# Sheet1.net
KiCad netlist of a schematic drawn in Altium Designer
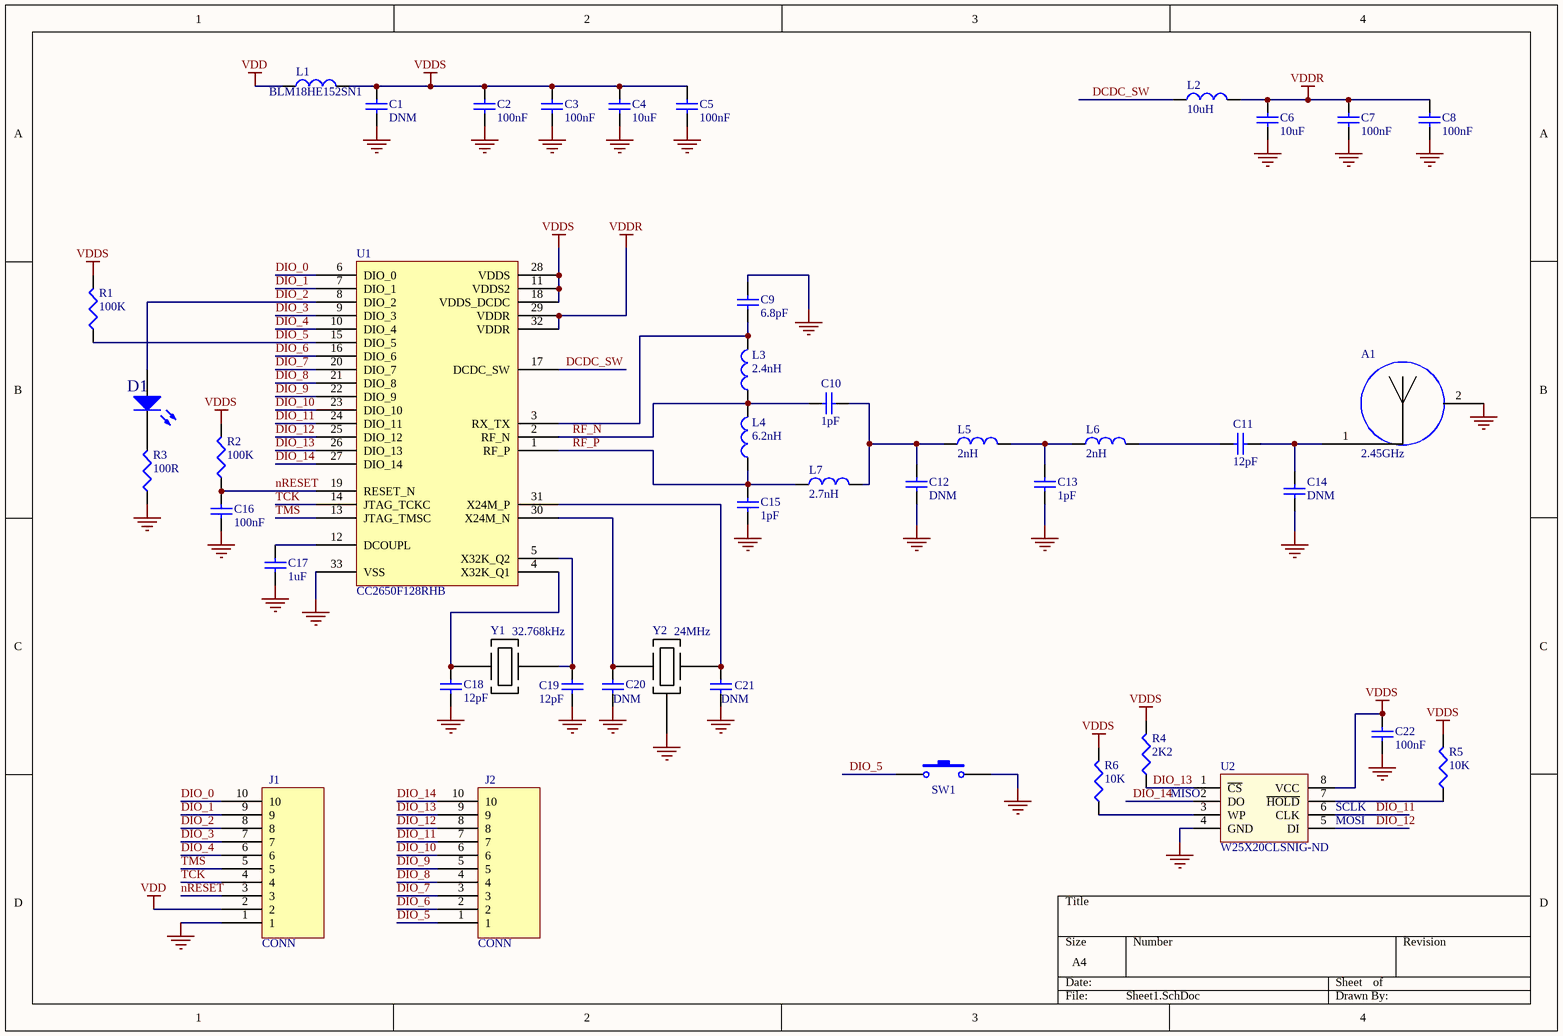
[diagram p0: Sheet1.SchDoc]

(export (version "E")
  (design (tool "Eeschema 10.0.6"))
  (components
    (comp (ref "A1")
      (value "2.45GHz")
      (footprint "ANTENNA_PCB_INATEL3")
      (description "ANTENNA 2.4GHz Freescale reference")
      (libsource (lib "Mechanical") (part "ANTENNA 2.4GHz_INATEL"))
    )
    (comp (ref "C1") (value "DNM") (footprint "0402") (libsource (lib "Schlib1") (part "CAP")))
    (comp (ref "C2")
      (value "100nF")
      (footprint "0402 - CAP")
      (description "CAP CER 0.1UF 6.3V 10% X7R 0402")
      (fields (field (name "MANUFACTURER") "Murata"))
      (libsource (lib "Schlib1") (part "CAP"))
    )
    (comp (ref "C3")
      (value "100nF")
      (footprint "0402 - CAP")
      (description "CAP CER 0.1UF 6.3V 10% X7R 0402")
      (fields (field (name "MANUFACTURER") "Murata"))
      (libsource (lib "Schlib1") (part "CAP"))
    )
    (comp (ref "C4")
      (value "10uF")
      (footprint "0603 - CAP")
      (description "CAP CER 10UF 6.3V 20% X5R 0603")
      (fields (field (name "MANUFACTURER") "Murata"))
      (libsource (lib "Schlib1") (part "CAP"))
    )
    (comp (ref "C5")
      (value "100nF")
      (footprint "0402 - CAP")
      (description "CAP CER 0.1UF 6.3V 10% X7R 0402")
      (fields (field (name "MANUFACTURER") "Murata"))
      (libsource (lib "Schlib1") (part "CAP"))
    )
    (comp (ref "C6")
      (value "10uF")
      (footprint "0603 - CAP")
      (description "CAP CER 10UF 6.3V 20% X5R 0603")
      (fields (field (name "MANUFACTURER") "Murata"))
      (libsource (lib "Schlib1") (part "CAP"))
    )
    (comp (ref "C7")
      (value "100nF")
      (footprint "0402 - CAP")
      (description "CAP CER 0.1UF 6.3V 10% X7R 0402")
      (fields (field (name "MANUFACTURER") "Murata"))
      (libsource (lib "Schlib1") (part "CAP"))
    )
    (comp (ref "C8")
      (value "100nF")
      (footprint "0402 - CAP")
      (description "CAP CER 0.1UF 6.3V 10% X7R 0402")
      (fields (field (name "MANUFACTURER") "Murata"))
      (libsource (lib "Schlib1") (part "CAP"))
    )
    (comp (ref "C9")
      (value "6.8pF")
      (footprint "0402 - CAP")
      (description "CAP CER 6.8PF 50V NP0 0402")
      (fields (field (name "MANUFACTURER") "Murata"))
      (libsource (lib "Schlib1") (part "CAP"))
    )
    (comp (ref "C10")
      (value "1pF")
      (footprint "0402 - CAP")
      (description "CAP CER 1PF 50V NP0 0402")
      (fields (field (name "MANUFACTURER") "Murata"))
      (libsource (lib "Schlib1") (part "CAP"))
    )
    (comp (ref "C11")
      (value "12pF")
      (footprint "0402 - CAP")
      (description "CAP CER 12PF 50V NP0 0402")
      (fields (field (name "MANUFACTURER") "Murata"))
      (libsource (lib "Schlib1") (part "CAP"))
    )
    (comp (ref "C12") (value "DNM") (footprint "0402") (libsource (lib "Schlib1") (part "CAP")))
    (comp (ref "C13")
      (value "1pF")
      (footprint "0402 - CAP")
      (description "CAP CER 1PF 50V NP0 0402")
      (fields (field (name "MANUFACTURER") "Murata"))
      (libsource (lib "Schlib1") (part "CAP"))
    )
    (comp (ref "C14") (value "DNM") (footprint "0402") (libsource (lib "Schlib1") (part "CAP")))
    (comp (ref "C15")
      (value "1pF")
      (footprint "0402 - CAP")
      (description "CAP CER 1PF 50V NP0 0402")
      (fields (field (name "MANUFACTURER") "Murata"))
      (libsource (lib "Schlib1") (part "CAP"))
    )
    (comp (ref "C16")
      (value "100nF")
      (footprint "0402 - CAP")
      (description "CAP CER 0.1UF 6.3V 10% X7R 0402")
      (fields (field (name "MANUFACTURER") "Murata"))
      (libsource (lib "Schlib1") (part "CAP"))
    )
    (comp (ref "C17")
      (value "1uF")
      (footprint "0402 - CAP")
      (description "CAP CER 1UF 10V 10% X5R 0402")
      (fields (field (name "MANUFACTURER") "Murata"))
      (libsource (lib "Schlib1") (part "CAP"))
    )
    (comp (ref "C18")
      (value "12pF")
      (footprint "0402 - CAP")
      (description "CAP CER 12PF 50V NP0 0402")
      (fields (field (name "MANUFACTURER") "Murata"))
      (libsource (lib "Schlib1") (part "CAP"))
    )
    (comp (ref "C19")
      (value "12pF")
      (footprint "0402 - CAP")
      (description "CAP CER 12PF 50V NP0 0402")
      (fields (field (name "MANUFACTURER") "Murata"))
      (libsource (lib "Schlib1") (part "CAP"))
    )
    (comp (ref "C20") (value "DNM") (footprint "0402") (libsource (lib "Schlib1") (part "CAP")))
    (comp (ref "C21") (value "DNM") (footprint "0402") (libsource (lib "Schlib1") (part "CAP")))
    (comp (ref "C22")
      (value "100nF")
      (footprint "0402 - CAP")
      (description "CAP CER 0.1UF 6.3V 10% X7R 0402")
      (fields (field (name "MANUFACTURER") "Murata"))
      (libsource (lib "Schlib1") (part "CAP"))
    )
    (comp (ref "D1")
      (value "Status")
      (footprint "0603 - LED")
      (description "LED SUPER RED CLR THIN 0603 SMD")
      (fields (field (name "MANUFACTURER") "Lite-On Inc"))
      (libsource (lib "Schlib1") (part "LED_R"))
    )
    (comp (ref "J1")
      (value "CONN")
      (footprint "CONN_HEADER ARDUINO SHIELD")
      (description "10POS SIL VERTICAL PIN HEADER")
      (fields (field (name "MANUFACTURER") "Harwin Inc"))
      (libsource (lib "Schlib1") (part "CONN"))
    )
    (comp (ref "J2")
      (value "CONN")
      (footprint "CONN_HEADER ARDUINO SHIELD")
      (description "10POS SIL VERTICAL PIN HEADER")
      (fields (field (name "MANUFACTURER") "Harwin Inc"))
      (libsource (lib "Schlib1") (part "CONN"))
    )
    (comp (ref "L1")
      (value "BLM18HE152SN1")
      (footprint "0603 - IND")
      (description "FERRITE CHIP 1500 OHM 500MA 0603")
      (fields (field (name "MANUFACTURER") "Murata"))
      (libsource (lib "Schlib1") (part "INDUCTOR"))
    )
    (comp (ref "L2")
      (value "10uH")
      (footprint "0805 - CAP")
      (description "FIXED IND 10UH 110MA 520 MOHM")
      (fields (field (name "MANUFACTURER") "Taiyo Yuden"))
      (libsource (lib "Schlib1") (part "INDUCTOR"))
    )
    (comp (ref "L3")
      (value "2.4nH")
      (footprint "0402 - IND")
      (description "FIXED IND 2.4NH 300MA 160 MOHM")
      (fields (field (name "MANUFACTURER") "Murata"))
      (libsource (lib "") (part "INDUCTOR_1"))
    )
    (comp (ref "L4")
      (value "6.2nH")
      (footprint "0402 - IND")
      (description "FIXED IND 6.2NH 300MA 220 MOHM")
      (fields (field (name "MANUFACTURER") "Murata"))
      (libsource (lib "Schlib1") (part "INDUCTOR"))
    )
    (comp (ref "L5")
      (value "2nH")
      (footprint "0402 - IND")
      (description "FIXED IND 2NH 300MA 100 MOHM SMD")
      (fields (field (name "MANUFACTURER") "Murata"))
      (libsource (lib "Schlib1") (part "INDUCTOR"))
    )
    (comp (ref "L6")
      (value "2nH")
      (footprint "0402 - IND")
      (description "FIXED IND 2NH 300MA 100 MOHM SMD")
      (fields (field (name "MANUFACTURER") "Murata"))
      (libsource (lib "Schlib1") (part "INDUCTOR"))
    )
    (comp (ref "L7")
      (value "2.7nH")
      (footprint "0402 - IND")
      (description "FIXED IND 2.7NH 300MA 150 MOHM")
      (fields (field (name "MANUFACTURER") "Murata"))
      (libsource (lib "Schlib1") (part "INDUCTOR"))
    )
    (comp (ref "R1")
      (value "100K")
      (footprint "0402 - RES")
      (description "RES SMD 100K OHM 5% 1/10W 0402")
      (fields (field (name "MANUFACTURER") "Panasonic"))
      (libsource (lib "Schlib1") (part "RES"))
    )
    (comp (ref "R2")
      (value "100K")
      (footprint "0402 - RES")
      (description "RES SMD 100K OHM 5% 1/10W 0402")
      (fields (field (name "MANUFACTURER") "Panasonic"))
      (libsource (lib "Schlib1") (part "RES"))
    )
    (comp (ref "R3")
      (value "100R")
      (footprint "0402 - RES")
      (description "RES SMD 100 OHM 5% 1/10W 0402")
      (fields (field (name "MANUFACTURER") "Panasonic"))
      (libsource (lib "Schlib1") (part "RES"))
    )
    (comp (ref "R4")
      (value "2K2")
      (footprint "0402 - RES")
      (description "RES SMD 2.2K OHM 5% 1/10W 0402")
      (fields (field (name "MANUFACTURER") "Panasonic"))
      (libsource (lib "Schlib1") (part "RES"))
    )
    (comp (ref "R5")
      (value "10K")
      (footprint "0402 - RES")
      (description "RES SMD 10K OHM 5% 1/10W 0402")
      (fields (field (name "MANUFACTURER") "Panasonic"))
      (libsource (lib "Schlib1") (part "RES"))
    )
    (comp (ref "R6")
      (value "10K")
      (footprint "0402 - RES")
      (description "RES SMD 10K OHM 5% 1/10W 0402")
      (fields (field (name "MANUFACTURER") "Panasonic"))
      (libsource (lib "Schlib1") (part "RES"))
    )
    (comp (ref "SW1")
      (value "~")
      (footprint "EVP-AWCA2A")
      (description "SW")
      (libsource (lib "Mechanical") (part "SW_EVPAW"))
    )
    (comp (ref "U1")
      (value "CC2650F128RHB")
      (footprint "CC2650F128RHB - cm")
      (description "IC MCU 128KB FLASH PHY 32VQFN")
      (fields (field (name "MANUFACTURER") "TI"))
      (libsource (lib "Schlib1") (part "CC2650F128RHB"))
    )
    (comp (ref "U2")
      (value "W25X20CLSNIG-ND")
      (footprint "SOIC-8")
      (description "IC FLASH 2MBIT 104MHZ 8SOIC")
      (fields (field (name "MANUFACTURER") "Winbond"))
      (libsource (lib "Schlib1") (part "SPI_FLASH_SOIC_8"))
    )
    (comp (ref "Y1")
      (value "32.768kHz")
      (footprint "FC-12M")
      (description "Crystal 32.7680kHz 20ppm 12.5pF 90 kOhm -40°C - 85°C Surface Mount 2-SMD")
      (fields (field (name "MANUFACTURER") "EPSON"))
      (libsource (lib "") (part "XTAL1_1"))
    )
    (comp (ref "Y2")
      (value "24MHz")
      (footprint "XT_DFN_LCC_32x25")
      (description "Crystal 24.0000MHz 10ppm 9pF 40 Ohm -40°C - 85°C Surface Mount 4-SMD, No Lead (DFN, LCC)")
      (fields (field (name "MANUFACTURER") "EPSON"))
      (libsource (lib "Schlib1") (part "XTAL1"))
    )
  )
  (nets
    (net (code "1") (name "/DCDC_SW") (class "Default")
      (node (ref "L2") (pin "2") (pinfunction "2_2") (pintype "passive"))
      (node (ref "U1") (pin "17") (pinfunction "DCDC_SW_17") (pintype "passive"))
    )
    (net (code "2") (name "/DIO_0") (class "Default")
      (node (ref "J2") (pin "10") (pinfunction "10_10") (pintype "passive"))
      (node (ref "U1") (pin "6") (pinfunction "DIO_0_6") (pintype "passive"))
    )
    (net (code "3") (name "/DIO_1") (class "Default")
      (node (ref "J2") (pin "9") (pinfunction "9_9") (pintype "passive"))
      (node (ref "U1") (pin "7") (pinfunction "DIO_1_7") (pintype "passive"))
    )
    (net (code "4") (name "/DIO_2") (class "Default")
      (node (ref "D1") (pin "1") (pinfunction "A_1") (pintype "passive"))
      (node (ref "J2") (pin "8") (pinfunction "8_8") (pintype "passive"))
      (node (ref "U1") (pin "8") (pinfunction "DIO_2_8") (pintype "passive"))
    )
    (net (code "5") (name "/DIO_3") (class "Default")
      (node (ref "J2") (pin "7") (pinfunction "7_7") (pintype "passive"))
      (node (ref "U1") (pin "9") (pinfunction "DIO_3_9") (pintype "passive"))
    )
    (net (code "6") (name "/DIO_4") (class "Default")
      (node (ref "J2") (pin "6") (pinfunction "6_6") (pintype "passive"))
      (node (ref "U1") (pin "10") (pinfunction "DIO_4_10") (pintype "passive"))
    )
    (net (code "7") (name "/DIO_5") (class "Default")
      (node (ref "J1") (pin "1") (pinfunction "1_1") (pintype "passive"))
      (node (ref "R1") (pin "1") (pinfunction "1_1") (pintype "passive"))
      (node (ref "SW1") (pin "1") (pinfunction "1_1") (pintype "passive"))
      (node (ref "U1") (pin "15") (pinfunction "DIO_5_15") (pintype "passive"))
    )
    (net (code "8") (name "/DIO_6") (class "Default")
      (node (ref "J1") (pin "2") (pinfunction "2_2") (pintype "passive"))
      (node (ref "U1") (pin "16") (pinfunction "DIO_6_16") (pintype "passive"))
    )
    (net (code "9") (name "/DIO_7") (class "Default")
      (node (ref "J1") (pin "3") (pinfunction "3_3") (pintype "passive"))
      (node (ref "U1") (pin "20") (pinfunction "DIO_7_20") (pintype "passive"))
    )
    (net (code "10") (name "/DIO_8") (class "Default")
      (node (ref "J1") (pin "4") (pinfunction "4_4") (pintype "passive"))
      (node (ref "U1") (pin "21") (pinfunction "DIO_8_21") (pintype "passive"))
    )
    (net (code "11") (name "/DIO_9") (class "Default")
      (node (ref "J1") (pin "5") (pinfunction "5_5") (pintype "passive"))
      (node (ref "U1") (pin "22") (pinfunction "DIO_9_22") (pintype "passive"))
    )
    (net (code "12") (name "/DIO_10") (class "Default")
      (node (ref "J1") (pin "6") (pinfunction "6_6") (pintype "passive"))
      (node (ref "U1") (pin "23") (pinfunction "DIO_10_23") (pintype "passive"))
    )
    (net (code "13") (name "/DIO_11") (class "Default")
      (node (ref "J1") (pin "7") (pinfunction "7_7") (pintype "passive"))
      (node (ref "U1") (pin "24") (pinfunction "DIO_11_24") (pintype "passive"))
      (node (ref "U2") (pin "6") (pinfunction "CLK_6") (pintype "passive"))
    )
    (net (code "14") (name "/DIO_12") (class "Default")
      (node (ref "J1") (pin "8") (pinfunction "8_8") (pintype "passive"))
      (node (ref "U1") (pin "25") (pinfunction "DIO_12_25") (pintype "passive"))
      (node (ref "U2") (pin "5") (pinfunction "DI_5") (pintype "passive"))
    )
    (net (code "15") (name "/DIO_13") (class "Default")
      (node (ref "J1") (pin "9") (pinfunction "9_9") (pintype "passive"))
      (node (ref "R4") (pin "1") (pinfunction "1_1") (pintype "passive"))
      (node (ref "U1") (pin "26") (pinfunction "DIO_13_26") (pintype "passive"))
      (node (ref "U2") (pin "1") (pinfunction "~{CS}_1") (pintype "passive"))
    )
    (net (code "16") (name "/DIO_14") (class "Default")
      (node (ref "J1") (pin "10") (pinfunction "10_10") (pintype "passive"))
      (node (ref "U1") (pin "27") (pinfunction "DIO_14_27") (pintype "passive"))
      (node (ref "U2") (pin "2") (pinfunction "DO_2") (pintype "passive"))
    )
    (net (code "17") (name "/RF_N") (class "Default")
      (node (ref "C10") (pin "2") (pinfunction "2_2") (pintype "passive"))
      (node (ref "L3") (pin "1") (pinfunction "1_1") (pintype "passive"))
      (node (ref "L4") (pin "1") (pinfunction "1_1") (pintype "passive"))
      (node (ref "U1") (pin "2") (pinfunction "RF_N_2") (pintype "passive"))
    )
    (net (code "18") (name "/RF_P") (class "Default")
      (node (ref "C15") (pin "1") (pinfunction "1_1") (pintype "passive"))
      (node (ref "L4") (pin "2") (pinfunction "2_2") (pintype "passive"))
      (node (ref "L7") (pin "2") (pinfunction "2_2") (pintype "passive"))
      (node (ref "U1") (pin "1") (pinfunction "RF_P_1") (pintype "passive"))
    )
    (net (code "19") (name "/TCK") (class "Default")
      (node (ref "J2") (pin "4") (pinfunction "4_4") (pintype "passive"))
      (node (ref "U1") (pin "14") (pinfunction "JTAG_TCKC_14") (pintype "passive"))
    )
    (net (code "20") (name "/TMS") (class "Default")
      (node (ref "J2") (pin "5") (pinfunction "5_5") (pintype "passive"))
      (node (ref "U1") (pin "13") (pinfunction "JTAG_TMSC_13") (pintype "passive"))
    )
    (net (code "21") (name "/nRESET") (class "Default")
      (node (ref "C16") (pin "2") (pinfunction "2_2") (pintype "passive"))
      (node (ref "J2") (pin "3") (pinfunction "3_3") (pintype "passive"))
      (node (ref "R2") (pin "1") (pinfunction "1_1") (pintype "passive"))
      (node (ref "U1") (pin "19") (pinfunction "RESET_N_19") (pintype "passive"))
    )
    (net (code "22") (name "GND") (class "Default")
      (node (ref "A1") (pin "2") (pinfunction "2_2") (pintype "passive"))
      (node (ref "C1") (pin "1") (pinfunction "1_1") (pintype "passive"))
      (node (ref "C12") (pin "1") (pinfunction "1_1") (pintype "passive"))
      (node (ref "C13") (pin "1") (pinfunction "1_1") (pintype "passive"))
      (node (ref "C14") (pin "1") (pinfunction "1_1") (pintype "passive"))
      (node (ref "C15") (pin "2") (pinfunction "2_2") (pintype "passive"))
      (node (ref "C16") (pin "1") (pinfunction "1_1") (pintype "passive"))
      (node (ref "C17") (pin "1") (pinfunction "1_1") (pintype "passive"))
      (node (ref "C18") (pin "1") (pinfunction "1_1") (pintype "passive"))
      (node (ref "C19") (pin "1") (pinfunction "1_1") (pintype "passive"))
      (node (ref "C2") (pin "1") (pinfunction "1_1") (pintype "passive"))
      (node (ref "C20") (pin "1") (pinfunction "1_1") (pintype "passive"))
      (node (ref "C21") (pin "1") (pinfunction "1_1") (pintype "passive"))
      (node (ref "C22") (pin "1") (pinfunction "1_1") (pintype "passive"))
      (node (ref "C3") (pin "1") (pinfunction "1_1") (pintype "passive"))
      (node (ref "C4") (pin "1") (pinfunction "1_1") (pintype "passive"))
      (node (ref "C5") (pin "1") (pinfunction "1_1") (pintype "passive"))
      (node (ref "C6") (pin "1") (pinfunction "1_1") (pintype "passive"))
      (node (ref "C7") (pin "1") (pinfunction "1_1") (pintype "passive"))
      (node (ref "C8") (pin "1") (pinfunction "1_1") (pintype "passive"))
      (node (ref "C9") (pin "2") (pinfunction "2_2") (pintype "passive"))
      (node (ref "J2") (pin "1") (pinfunction "1_1") (pintype "passive"))
      (node (ref "R3") (pin "1") (pinfunction "1_1") (pintype "passive"))
      (node (ref "SW1") (pin "2") (pinfunction "2_2") (pintype "passive"))
      (node (ref "U1") (pin "33") (pinfunction "VSS_33") (pintype "passive"))
      (node (ref "U2") (pin "4") (pinfunction "GND_4") (pintype "passive"))
      (node (ref "Y2") (pin "3") (pinfunction "3_3") (pintype "passive"))
    )
    (net (code "23") (name "Net-(A1-Pad1)") (class "Default")
      (node (ref "A1") (pin "1") (pinfunction "1_1") (pintype "passive"))
      (node (ref "C11") (pin "1") (pinfunction "1_1") (pintype "passive"))
      (node (ref "C14") (pin "2") (pinfunction "2_2") (pintype "passive"))
    )
    (net (code "24") (name "Net-(C10-Pad1)") (class "Default")
      (node (ref "C10") (pin "1") (pinfunction "1_1") (pintype "passive"))
      (node (ref "C12") (pin "2") (pinfunction "2_2") (pintype "passive"))
      (node (ref "L5") (pin "2") (pinfunction "2_2") (pintype "passive"))
      (node (ref "L7") (pin "1") (pinfunction "1_1") (pintype "passive"))
    )
    (net (code "25") (name "Net-(C11-Pad2)") (class "Default")
      (node (ref "C11") (pin "2") (pinfunction "2_2") (pintype "passive"))
      (node (ref "L6") (pin "1") (pinfunction "1_1") (pintype "passive"))
    )
    (net (code "26") (name "Net-(C13-Pad2)") (class "Default")
      (node (ref "C13") (pin "2") (pinfunction "2_2") (pintype "passive"))
      (node (ref "L5") (pin "1") (pinfunction "1_1") (pintype "passive"))
      (node (ref "L6") (pin "2") (pinfunction "2_2") (pintype "passive"))
    )
    (net (code "27") (name "Net-(D1-K)") (class "Default")
      (node (ref "D1") (pin "2") (pinfunction "K_2") (pintype "passive"))
      (node (ref "R3") (pin "2") (pinfunction "2_2") (pintype "passive"))
    )
    (net (code "28") (name "Net-(U1-DCOUPL)") (class "Default")
      (node (ref "C17") (pin "2") (pinfunction "2_2") (pintype "passive"))
      (node (ref "U1") (pin "12") (pinfunction "DCOUPL_12") (pintype "passive"))
    )
    (net (code "29") (name "Net-(U1-RX_TX)") (class "Default")
      (node (ref "C9") (pin "1") (pinfunction "1_1") (pintype "passive"))
      (node (ref "L3") (pin "2") (pinfunction "2_2") (pintype "passive"))
      (node (ref "U1") (pin "3") (pinfunction "RX_TX_3") (pintype "passive"))
    )
    (net (code "30") (name "Net-(U1-X24M_N)") (class "Default")
      (node (ref "C20") (pin "2") (pinfunction "2_2") (pintype "passive"))
      (node (ref "U1") (pin "30") (pinfunction "X24M_N_30") (pintype "passive"))
      (node (ref "Y2") (pin "1") (pinfunction "1_1") (pintype "passive"))
    )
    (net (code "31") (name "Net-(U1-X24M_P)") (class "Default")
      (node (ref "C21") (pin "2") (pinfunction "2_2") (pintype "passive"))
      (node (ref "U1") (pin "31") (pinfunction "X24M_P_31") (pintype "passive"))
      (node (ref "Y2") (pin "2") (pinfunction "2_2") (pintype "passive"))
    )
    (net (code "32") (name "Net-(U1-X32K_Q1)") (class "Default")
      (node (ref "C18") (pin "2") (pinfunction "2_2") (pintype "passive"))
      (node (ref "U1") (pin "4") (pinfunction "X32K_Q1_4") (pintype "passive"))
      (node (ref "Y1") (pin "1") (pinfunction "1_1") (pintype "passive"))
    )
    (net (code "33") (name "Net-(U1-X32K_Q2)") (class "Default")
      (node (ref "C19") (pin "2") (pinfunction "2_2") (pintype "passive"))
      (node (ref "U1") (pin "5") (pinfunction "X32K_Q2_5") (pintype "passive"))
      (node (ref "Y1") (pin "2") (pinfunction "2_2") (pintype "passive"))
    )
    (net (code "34") (name "Net-(U2-WP)") (class "Default")
      (node (ref "R6") (pin "1") (pinfunction "1_1") (pintype "passive"))
      (node (ref "U2") (pin "3") (pinfunction "WP_3") (pintype "passive"))
    )
    (net (code "35") (name "Net-(U2-~{HOLD})") (class "Default")
      (node (ref "R5") (pin "1") (pinfunction "1_1") (pintype "passive"))
      (node (ref "U2") (pin "7") (pinfunction "~{HOLD}_7") (pintype "passive"))
    )
    (net (code "36") (name "VDD") (class "Default")
      (node (ref "J2") (pin "2") (pinfunction "2_2") (pintype "passive"))
      (node (ref "L1") (pin "2") (pinfunction "2_2") (pintype "passive"))
    )
    (net (code "37") (name "VDDR") (class "Default")
      (node (ref "C6") (pin "2") (pinfunction "2_2") (pintype "passive"))
      (node (ref "C7") (pin "2") (pinfunction "2_2") (pintype "passive"))
      (node (ref "C8") (pin "2") (pinfunction "2_2") (pintype "passive"))
      (node (ref "L2") (pin "1") (pinfunction "1_1") (pintype "passive"))
      (node (ref "U1") (pin "29") (pinfunction "VDDR_29") (pintype "passive"))
      (node (ref "U1") (pin "32") (pinfunction "VDDR_32") (pintype "passive"))
    )
    (net (code "38") (name "VDDS") (class "Default")
      (node (ref "C1") (pin "2") (pinfunction "2_2") (pintype "passive"))
      (node (ref "C2") (pin "2") (pinfunction "2_2") (pintype "passive"))
      (node (ref "C22") (pin "2") (pinfunction "2_2") (pintype "passive"))
      (node (ref "C3") (pin "2") (pinfunction "2_2") (pintype "passive"))
      (node (ref "C4") (pin "2") (pinfunction "2_2") (pintype "passive"))
      (node (ref "C5") (pin "2") (pinfunction "2_2") (pintype "passive"))
      (node (ref "L1") (pin "1") (pinfunction "1_1") (pintype "passive"))
      (node (ref "R1") (pin "2") (pinfunction "2_2") (pintype "passive"))
      (node (ref "R2") (pin "2") (pinfunction "2_2") (pintype "passive"))
      (node (ref "R4") (pin "2") (pinfunction "2_2") (pintype "passive"))
      (node (ref "R5") (pin "2") (pinfunction "2_2") (pintype "passive"))
      (node (ref "R6") (pin "2") (pinfunction "2_2") (pintype "passive"))
      (node (ref "U1") (pin "11") (pinfunction "VDDS2_11") (pintype "passive"))
      (node (ref "U1") (pin "18") (pinfunction "VDDS_DCDC_18") (pintype "passive"))
      (node (ref "U1") (pin "28") (pinfunction "VDDS_28") (pintype "passive"))
      (node (ref "U2") (pin "8") (pinfunction "VCC_8") (pintype "passive"))
    )
    (net (code "39") (name "unconnected-(Y1-Pad3)") (class "Default")
      (node (ref "Y1") (pin "3") (pinfunction "3_3") (pintype "passive"))
    )
  )
)
